# TI_TS5Axx.net
KiCad netlist of a schematic drawn in EAGLE
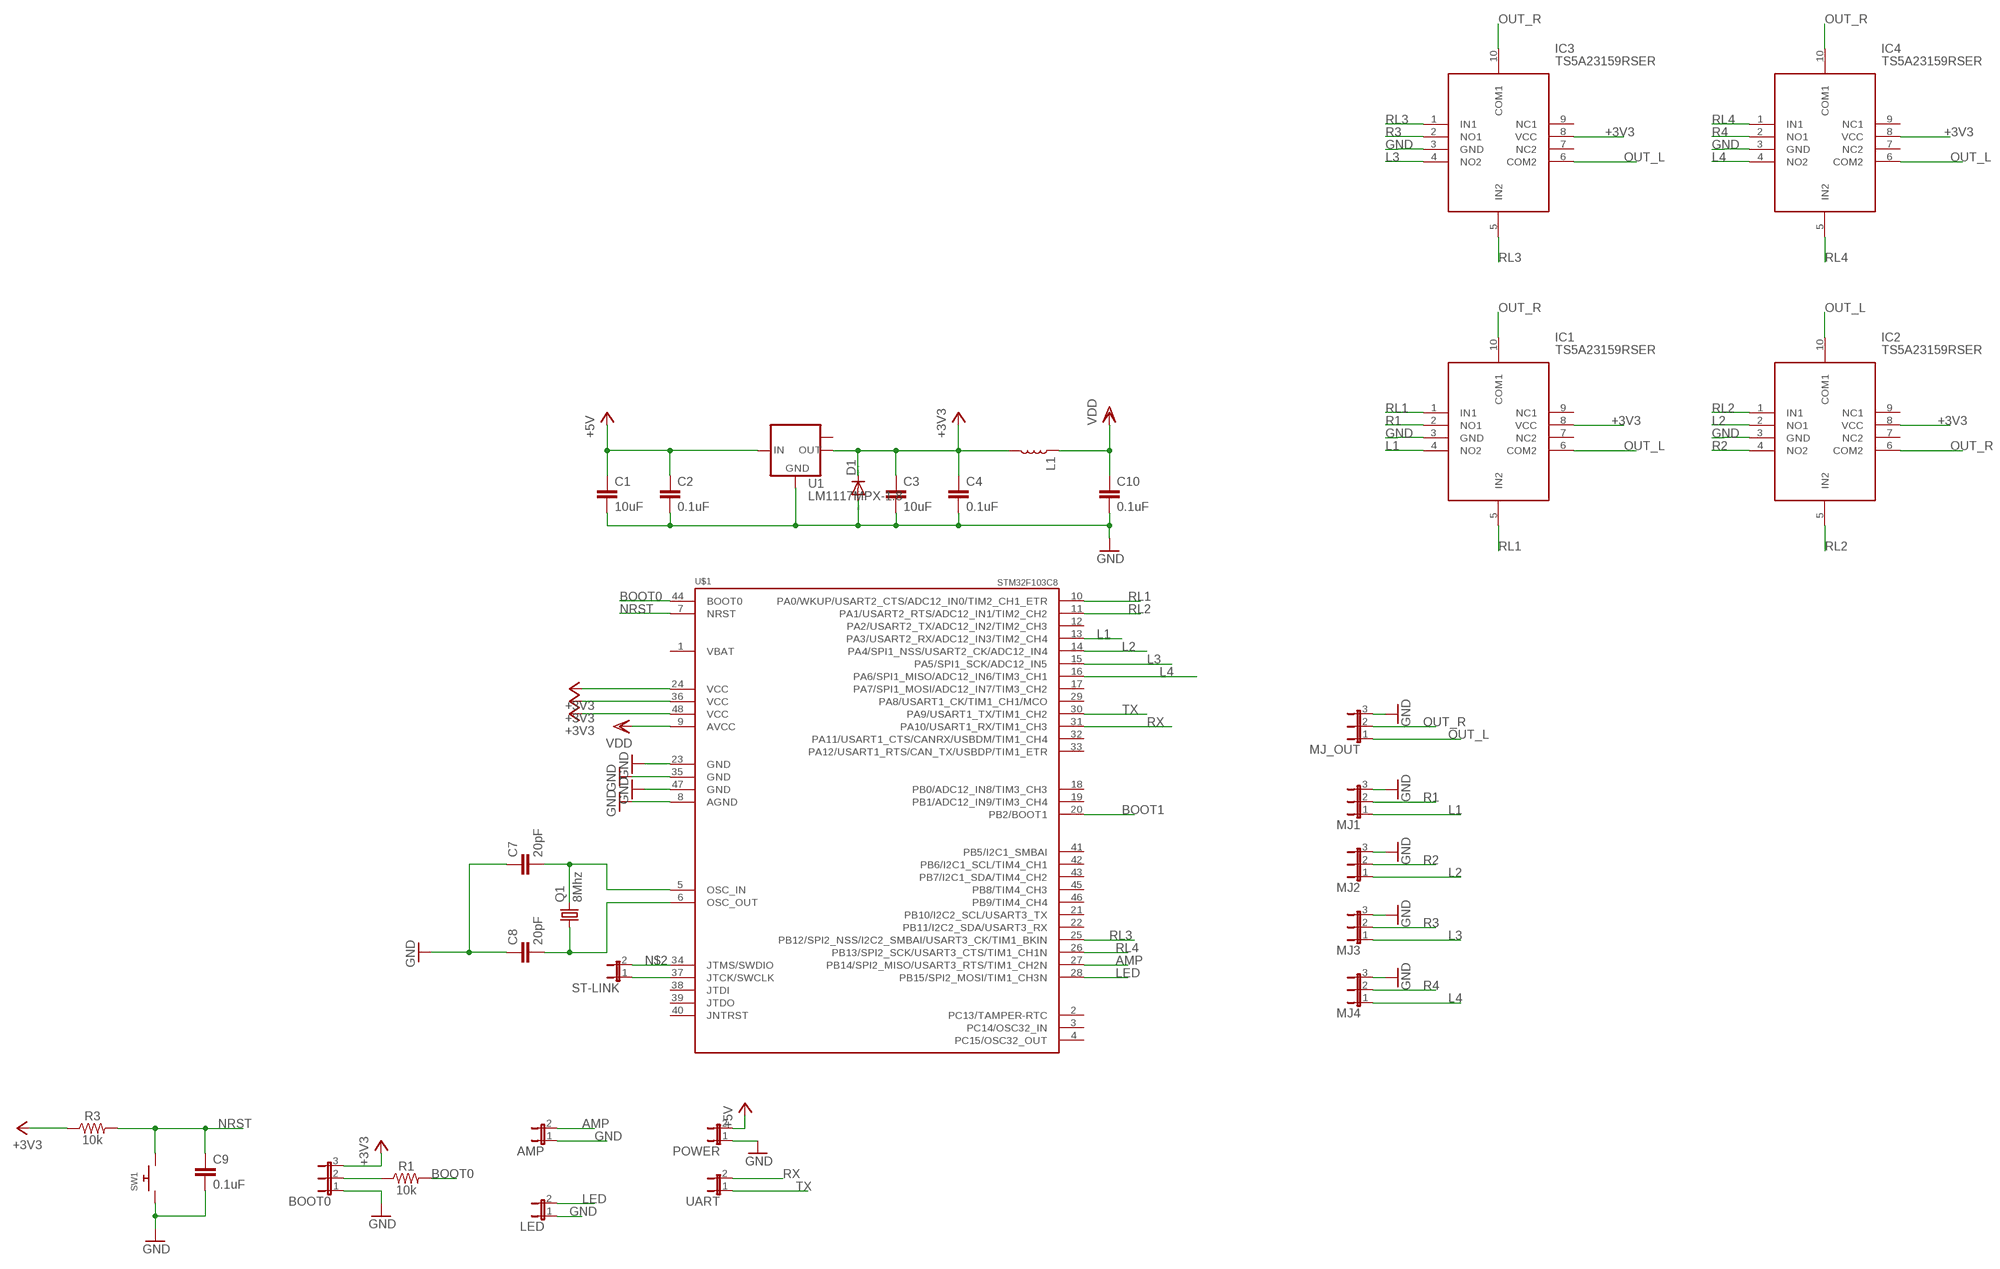
[diagram p0: schematic, sheet 1]

(export (version "E")
  (design (tool "Eeschema 10.0.6"))
  (components
    (comp (ref "AMP")
      (value "JP1E")
      (footprint "eagle-import:JP1")
      (libsource (lib "eagle-import") (part "JP1E"))
    )
    (comp (ref "BOOT0")
      (value "JP2E")
      (footprint "eagle-import:JP2")
      (libsource (lib "eagle-import") (part "JP2E"))
    )
    (comp (ref "C1")
      (value "10uF")
      (footprint "eagle-import:0805")
      (libsource (lib "eagle-import") (part "10UF-0805-10V-10%"))
    )
    (comp (ref "C2")
      (value "0.1uF")
      (footprint "eagle-import:0805")
      (libsource (lib "eagle-import") (part "10UF-0805-10V-10%"))
    )
    (comp (ref "C3")
      (value "10uF")
      (footprint "eagle-import:0805")
      (libsource (lib "eagle-import") (part "10UF-0805-10V-10%"))
    )
    (comp (ref "C4")
      (value "0.1uF")
      (footprint "eagle-import:0805")
      (libsource (lib "eagle-import") (part "10UF-0805-10V-10%"))
    )
    (comp (ref "C7")
      (value "20pF")
      (footprint "eagle-import:0805")
      (libsource (lib "eagle-import") (part "0.33UF/330NF-0805-50V-10%"))
    )
    (comp (ref "C8")
      (value "20pF")
      (footprint "eagle-import:0805")
      (libsource (lib "eagle-import") (part "0.33UF/330NF-0805-50V-10%"))
    )
    (comp (ref "C9")
      (value "0.1uF")
      (footprint "eagle-import:0805")
      (libsource (lib "eagle-import") (part "10UF-0805-10V-10%"))
    )
    (comp (ref "C10")
      (value "0.1uF")
      (footprint "eagle-import:0805")
      (libsource (lib "eagle-import") (part "10UF-0805-10V-10%"))
    )
    (comp (ref "D1")
      (value "DIODE-DO214AA")
      (footprint "eagle-import:DO214AA")
      (libsource (lib "eagle-import") (part "DIODE-DO214AA"))
    )
    (comp (ref "IC1")
      (value "TS5A23159RSER")
      (footprint "eagle-import:QFN50P150X200X60-10N")
      (libsource (lib "eagle-import") (part "TS5A23159RSER"))
    )
    (comp (ref "IC2")
      (value "TS5A23159RSER")
      (footprint "eagle-import:QFN50P150X200X60-10N")
      (libsource (lib "eagle-import") (part "TS5A23159RSER"))
    )
    (comp (ref "IC3")
      (value "TS5A23159RSER")
      (footprint "eagle-import:QFN50P150X200X60-10N")
      (libsource (lib "eagle-import") (part "TS5A23159RSER"))
    )
    (comp (ref "IC4")
      (value "TS5A23159RSER")
      (footprint "eagle-import:QFN50P150X200X60-10N")
      (libsource (lib "eagle-import") (part "TS5A23159RSER"))
    )
    (comp (ref "L1")
      (value "INDUCTORFB-30OHM")
      (footprint "eagle-import:0603")
      (libsource (lib "eagle-import") (part "INDUCTORFB-30OHM"))
    )
    (comp (ref "LED")
      (value "JP1E")
      (footprint "eagle-import:JP1")
      (libsource (lib "eagle-import") (part "JP1E"))
    )
    (comp (ref "MJ1")
      (value "JP2E")
      (footprint "eagle-import:JP2")
      (libsource (lib "eagle-import") (part "JP2E"))
    )
    (comp (ref "MJ2")
      (value "JP2E")
      (footprint "eagle-import:JP2")
      (libsource (lib "eagle-import") (part "JP2E"))
    )
    (comp (ref "MJ3")
      (value "JP2E")
      (footprint "eagle-import:JP2")
      (libsource (lib "eagle-import") (part "JP2E"))
    )
    (comp (ref "MJ4")
      (value "JP2E")
      (footprint "eagle-import:JP2")
      (libsource (lib "eagle-import") (part "JP2E"))
    )
    (comp (ref "MJ_OUT")
      (value "JP2E")
      (footprint "eagle-import:JP2")
      (libsource (lib "eagle-import") (part "JP2E"))
    )
    (comp (ref "POWER")
      (value "JP1E")
      (footprint "eagle-import:JP1")
      (libsource (lib "eagle-import") (part "JP1E"))
    )
    (comp (ref "Q1")
      (value "8Mhz")
      (footprint "eagle-import:HC49_S")
      (libsource (lib "eagle-import") (part "CRYSTALHC49S"))
    )
    (comp (ref "R1")
      (value "10k")
      (footprint "eagle-import:0603")
      (libsource (lib "eagle-import") (part "10KOHM-0603-1/10W-1%"))
    )
    (comp (ref "R3")
      (value "10k")
      (footprint "eagle-import:0603")
      (libsource (lib "eagle-import") (part "10KOHM-0603-1/10W-1%"))
    )
    (comp (ref "ST-LINK")
      (value "JP1E")
      (footprint "eagle-import:JP1")
      (libsource (lib "eagle-import") (part "JP1E"))
    )
    (comp (ref "SW1")
      (value "SWITCH_PUSHBUTTONEVQ-PE")
      (footprint "eagle-import:TACT_PANA-EVQ")
      (libsource (lib "eagle-import") (part "SWITCH_PUSHBUTTONEVQ-PE"))
    )
    (comp (ref "U$1")
      (value "STM32F103C8")
      (footprint "eagle-import:LQFP48-7X7")
      (libsource (lib "eagle-import") (part "STM32F103C8"))
    )
    (comp (ref "U1")
      (value "LM1117MPX-1.8")
      (footprint "eagle-import:SOT223")
      (libsource (lib "eagle-import") (part "LM1117MPX-1.8"))
    )
    (comp (ref "UART")
      (value "JP1E")
      (footprint "eagle-import:JP1")
      (libsource (lib "eagle-import") (part "JP1E"))
    )
  )
  (nets
    (net (code "1") (name "+3V3") (class "Default")
      (node (ref "BOOT0") (pin "3") (pinfunction "3_3") (pintype "passive"))
      (node (ref "C3") (pin "1") (pinfunction "1_1") (pintype "passive"))
      (node (ref "C4") (pin "1") (pinfunction "1_1") (pintype "passive"))
      (node (ref "D1") (pin "C") (pinfunction "C_C") (pintype "passive"))
      (node (ref "IC1") (pin "8") (pinfunction "VCC_8") (pintype "bidirectional"))
      (node (ref "IC2") (pin "8") (pinfunction "VCC_8") (pintype "bidirectional"))
      (node (ref "IC3") (pin "8") (pinfunction "VCC_8") (pintype "bidirectional"))
      (node (ref "IC4") (pin "8") (pinfunction "VCC_8") (pintype "bidirectional"))
      (node (ref "L1") (pin "2") (pinfunction "2_2") (pintype "passive"))
      (node (ref "R3") (pin "1") (pinfunction "1_1") (pintype "passive"))
      (node (ref "U$1") (pin "24") (pinfunction "VCC_24") (pintype "power_in"))
      (node (ref "U$1") (pin "36") (pinfunction "VCC_36") (pintype "power_in"))
      (node (ref "U$1") (pin "48") (pinfunction "VCC_48") (pintype "power_in"))
      (node (ref "U1") (pin "2") (pinfunction "OUT_2") (pintype "passive"))
    )
    (net (code "2") (name "+5V") (class "Default")
      (node (ref "C1") (pin "1") (pinfunction "1_1") (pintype "passive"))
      (node (ref "C2") (pin "1") (pinfunction "1_1") (pintype "passive"))
      (node (ref "POWER") (pin "2") (pinfunction "2_2") (pintype "passive"))
      (node (ref "U1") (pin "3") (pinfunction "IN_3") (pintype "input"))
    )
    (net (code "3") (name "/AMP") (class "Default")
      (node (ref "AMP") (pin "2") (pinfunction "2_2") (pintype "passive"))
      (node (ref "U$1") (pin "27") (pinfunction "PB14/SPI2_MISO/USART3_RTS/TIM1_CH2N_27") (pintype "bidirectional"))
    )
    (net (code "4") (name "/BOOT0") (class "Default")
      (node (ref "R1") (pin "2") (pinfunction "2_2") (pintype "passive"))
      (node (ref "U$1") (pin "44") (pinfunction "BOOT0_44") (pintype "bidirectional"))
    )
    (net (code "5") (name "/BOOT1") (class "Default")
      (node (ref "U$1") (pin "20") (pinfunction "PB2/BOOT1_20") (pintype "bidirectional"))
    )
    (net (code "6") (name "/L1") (class "Default")
      (node (ref "IC1") (pin "4") (pinfunction "NO2_4") (pintype "bidirectional"))
      (node (ref "MJ1") (pin "1") (pinfunction "1_1") (pintype "passive"))
      (node (ref "U$1") (pin "13") (pinfunction "PA3/USART2_RX/ADC12_IN3/TIM2_CH4_13") (pintype "bidirectional"))
    )
    (net (code "7") (name "/L2") (class "Default")
      (node (ref "IC2") (pin "2") (pinfunction "NO1_2") (pintype "bidirectional"))
      (node (ref "MJ2") (pin "1") (pinfunction "1_1") (pintype "passive"))
      (node (ref "U$1") (pin "14") (pinfunction "PA4/SPI1_NSS/USART2_CK/ADC12_IN4_14") (pintype "bidirectional"))
    )
    (net (code "8") (name "/L3") (class "Default")
      (node (ref "IC3") (pin "4") (pinfunction "NO2_4") (pintype "bidirectional"))
      (node (ref "MJ3") (pin "1") (pinfunction "1_1") (pintype "passive"))
      (node (ref "U$1") (pin "15") (pinfunction "PA5/SPI1_SCK/ADC12_IN5_15") (pintype "bidirectional"))
    )
    (net (code "9") (name "/L4") (class "Default")
      (node (ref "IC4") (pin "4") (pinfunction "NO2_4") (pintype "bidirectional"))
      (node (ref "MJ4") (pin "1") (pinfunction "1_1") (pintype "passive"))
      (node (ref "U$1") (pin "16") (pinfunction "PA6/SPI1_MISO/ADC12_IN6/TIM3_CH1_16") (pintype "bidirectional"))
    )
    (net (code "10") (name "/LED") (class "Default")
      (node (ref "LED") (pin "2") (pinfunction "2_2") (pintype "passive"))
      (node (ref "U$1") (pin "28") (pinfunction "PB15/SPI2_MOSI/TIM1_CH3N_28") (pintype "bidirectional"))
    )
    (net (code "11") (name "/N$2") (class "Default")
      (node (ref "ST-LINK") (pin "2") (pinfunction "2_2") (pintype "passive"))
      (node (ref "U$1") (pin "34") (pinfunction "JTMS/SWDIO_34") (pintype "bidirectional"))
    )
    (net (code "12") (name "/NRST") (class "Default")
      (node (ref "C9") (pin "1") (pinfunction "1_1") (pintype "passive"))
      (node (ref "R3") (pin "2") (pinfunction "2_2") (pintype "passive"))
      (node (ref "SW1") (pin "P$2") (pinfunction "P$2_P$2") (pintype "passive"))
      (node (ref "U$1") (pin "7") (pinfunction "NRST_7") (pintype "bidirectional"))
    )
    (net (code "13") (name "/OUT_L") (class "Default")
      (node (ref "IC1") (pin "6") (pinfunction "COM2_6") (pintype "bidirectional"))
      (node (ref "IC2") (pin "10") (pinfunction "COM1_10") (pintype "bidirectional"))
      (node (ref "IC3") (pin "6") (pinfunction "COM2_6") (pintype "bidirectional"))
      (node (ref "IC4") (pin "6") (pinfunction "COM2_6") (pintype "bidirectional"))
      (node (ref "MJ_OUT") (pin "1") (pinfunction "1_1") (pintype "passive"))
    )
    (net (code "14") (name "/OUT_R") (class "Default")
      (node (ref "IC1") (pin "10") (pinfunction "COM1_10") (pintype "bidirectional"))
      (node (ref "IC2") (pin "6") (pinfunction "COM2_6") (pintype "bidirectional"))
      (node (ref "IC3") (pin "10") (pinfunction "COM1_10") (pintype "bidirectional"))
      (node (ref "IC4") (pin "10") (pinfunction "COM1_10") (pintype "bidirectional"))
      (node (ref "MJ_OUT") (pin "2") (pinfunction "2_2") (pintype "passive"))
    )
    (net (code "15") (name "/R1") (class "Default")
      (node (ref "IC1") (pin "2") (pinfunction "NO1_2") (pintype "bidirectional"))
      (node (ref "MJ1") (pin "2") (pinfunction "2_2") (pintype "passive"))
    )
    (net (code "16") (name "/R2") (class "Default")
      (node (ref "IC2") (pin "4") (pinfunction "NO2_4") (pintype "bidirectional"))
      (node (ref "MJ2") (pin "2") (pinfunction "2_2") (pintype "passive"))
    )
    (net (code "17") (name "/R3") (class "Default")
      (node (ref "IC3") (pin "2") (pinfunction "NO1_2") (pintype "bidirectional"))
      (node (ref "MJ3") (pin "2") (pinfunction "2_2") (pintype "passive"))
    )
    (net (code "18") (name "/R4") (class "Default")
      (node (ref "IC4") (pin "2") (pinfunction "NO1_2") (pintype "bidirectional"))
      (node (ref "MJ4") (pin "2") (pinfunction "2_2") (pintype "passive"))
    )
    (net (code "19") (name "/RL1") (class "Default")
      (node (ref "IC1") (pin "1") (pinfunction "IN1_1") (pintype "bidirectional"))
      (node (ref "IC1") (pin "5") (pinfunction "IN2_5") (pintype "bidirectional"))
      (node (ref "U$1") (pin "10") (pinfunction "PA0/WKUP/USART2_CTS/ADC12_IN0/TIM2_CH1_ETR_10") (pintype "bidirectional"))
    )
    (net (code "20") (name "/RL2") (class "Default")
      (node (ref "IC2") (pin "1") (pinfunction "IN1_1") (pintype "bidirectional"))
      (node (ref "IC2") (pin "5") (pinfunction "IN2_5") (pintype "bidirectional"))
      (node (ref "U$1") (pin "11") (pinfunction "PA1/USART2_RTS/ADC12_IN1/TIM2_CH2_11") (pintype "bidirectional"))
    )
    (net (code "21") (name "/RL3") (class "Default")
      (node (ref "IC3") (pin "1") (pinfunction "IN1_1") (pintype "bidirectional"))
      (node (ref "IC3") (pin "5") (pinfunction "IN2_5") (pintype "bidirectional"))
      (node (ref "U$1") (pin "25") (pinfunction "PB12/SPI2_NSS/I2C2_SMBAI/USART3_CK/TIM1_BKIN_25") (pintype "bidirectional"))
    )
    (net (code "22") (name "/RL4") (class "Default")
      (node (ref "IC4") (pin "1") (pinfunction "IN1_1") (pintype "bidirectional"))
      (node (ref "IC4") (pin "5") (pinfunction "IN2_5") (pintype "bidirectional"))
      (node (ref "U$1") (pin "26") (pinfunction "PB13/SPI2_SCK/USART3_CTS/TIM1_CH1N_26") (pintype "bidirectional"))
    )
    (net (code "23") (name "/RX") (class "Default")
      (node (ref "U$1") (pin "31") (pinfunction "PA10/USART1_RX/TIM1_CH3_31") (pintype "bidirectional"))
      (node (ref "UART") (pin "2") (pinfunction "2_2") (pintype "passive"))
    )
    (net (code "24") (name "/TX") (class "Default")
      (node (ref "U$1") (pin "30") (pinfunction "PA9/USART1_TX/TIM1_CH2_30") (pintype "bidirectional"))
      (node (ref "UART") (pin "1") (pinfunction "1_1") (pintype "passive"))
    )
    (net (code "25") (name "/VBAT") (class "Default")
      (node (ref "U$1") (pin "1") (pinfunction "VBAT_1") (pintype "power_in"))
    )
    (net (code "26") (name "GND") (class "Default")
      (node (ref "AMP") (pin "1") (pinfunction "1_1") (pintype "passive"))
      (node (ref "BOOT0") (pin "1") (pinfunction "1_1") (pintype "passive"))
      (node (ref "C1") (pin "2") (pinfunction "2_2") (pintype "passive"))
      (node (ref "C10") (pin "2") (pinfunction "2_2") (pintype "passive"))
      (node (ref "C2") (pin "2") (pinfunction "2_2") (pintype "passive"))
      (node (ref "C3") (pin "2") (pinfunction "2_2") (pintype "passive"))
      (node (ref "C4") (pin "2") (pinfunction "2_2") (pintype "passive"))
      (node (ref "C7") (pin "1") (pinfunction "1_1") (pintype "passive"))
      (node (ref "C8") (pin "1") (pinfunction "1_1") (pintype "passive"))
      (node (ref "C9") (pin "2") (pinfunction "2_2") (pintype "passive"))
      (node (ref "D1") (pin "A") (pinfunction "A_A") (pintype "passive"))
      (node (ref "IC1") (pin "3") (pinfunction "GND_3") (pintype "bidirectional"))
      (node (ref "IC2") (pin "3") (pinfunction "GND_3") (pintype "bidirectional"))
      (node (ref "IC3") (pin "3") (pinfunction "GND_3") (pintype "bidirectional"))
      (node (ref "IC4") (pin "3") (pinfunction "GND_3") (pintype "bidirectional"))
      (node (ref "LED") (pin "1") (pinfunction "1_1") (pintype "passive"))
      (node (ref "MJ1") (pin "3") (pinfunction "3_3") (pintype "passive"))
      (node (ref "MJ2") (pin "3") (pinfunction "3_3") (pintype "passive"))
      (node (ref "MJ3") (pin "3") (pinfunction "3_3") (pintype "passive"))
      (node (ref "MJ4") (pin "3") (pinfunction "3_3") (pintype "passive"))
      (node (ref "MJ_OUT") (pin "3") (pinfunction "3_3") (pintype "passive"))
      (node (ref "POWER") (pin "1") (pinfunction "1_1") (pintype "passive"))
      (node (ref "SW1") (pin "P$1") (pinfunction "P$1_P$1") (pintype "passive"))
      (node (ref "U$1") (pin "23") (pinfunction "GND_23") (pintype "power_in"))
      (node (ref "U$1") (pin "35") (pinfunction "GND_35") (pintype "power_in"))
      (node (ref "U$1") (pin "47") (pinfunction "GND_47") (pintype "power_in"))
      (node (ref "U$1") (pin "8") (pinfunction "AGND_8") (pintype "power_in"))
      (node (ref "U1") (pin "1") (pinfunction "GND_1") (pintype "input"))
    )
    (net (code "27") (name "Net-(BOOT0-Pad2)") (class "Default")
      (node (ref "BOOT0") (pin "2") (pinfunction "2_2") (pintype "passive"))
      (node (ref "R1") (pin "1") (pinfunction "1_1") (pintype "passive"))
    )
    (net (code "28") (name "Net-(U$1-JTCK{slash}SWCLK)") (class "Default")
      (node (ref "ST-LINK") (pin "1") (pinfunction "1_1") (pintype "passive"))
      (node (ref "U$1") (pin "37") (pinfunction "JTCK/SWCLK_37") (pintype "bidirectional"))
    )
    (net (code "29") (name "Net-(U$1-OSC_IN)") (class "Default")
      (node (ref "C7") (pin "2") (pinfunction "2_2") (pintype "passive"))
      (node (ref "Q1") (pin "2") (pinfunction "2_2") (pintype "passive"))
      (node (ref "U$1") (pin "5") (pinfunction "OSC_IN_5") (pintype "input"))
    )
    (net (code "30") (name "Net-(U$1-OSC_OUT)") (class "Default")
      (node (ref "C8") (pin "2") (pinfunction "2_2") (pintype "passive"))
      (node (ref "Q1") (pin "1") (pinfunction "1_1") (pintype "passive"))
      (node (ref "U$1") (pin "6") (pinfunction "OSC_OUT_6") (pintype "output"))
    )
    (net (code "31") (name "VDD") (class "Default")
      (node (ref "C10") (pin "1") (pinfunction "1_1") (pintype "passive"))
      (node (ref "L1") (pin "1") (pinfunction "1_1") (pintype "passive"))
      (node (ref "U$1") (pin "9") (pinfunction "AVCC_9") (pintype "power_in"))
    )
    (net (code "32") (name "unconnected-(IC1-NC1-Pad9)") (class "Default")
      (node (ref "IC1") (pin "9") (pinfunction "NC1_9") (pintype "bidirectional"))
    )
    (net (code "33") (name "unconnected-(IC1-NC2-Pad7)") (class "Default")
      (node (ref "IC1") (pin "7") (pinfunction "NC2_7") (pintype "bidirectional"))
    )
    (net (code "34") (name "unconnected-(IC2-NC1-Pad9)") (class "Default")
      (node (ref "IC2") (pin "9") (pinfunction "NC1_9") (pintype "bidirectional"))
    )
    (net (code "35") (name "unconnected-(IC2-NC2-Pad7)") (class "Default")
      (node (ref "IC2") (pin "7") (pinfunction "NC2_7") (pintype "bidirectional"))
    )
    (net (code "36") (name "unconnected-(IC3-NC1-Pad9)") (class "Default")
      (node (ref "IC3") (pin "9") (pinfunction "NC1_9") (pintype "bidirectional"))
    )
    (net (code "37") (name "unconnected-(IC3-NC2-Pad7)") (class "Default")
      (node (ref "IC3") (pin "7") (pinfunction "NC2_7") (pintype "bidirectional"))
    )
    (net (code "38") (name "unconnected-(IC4-NC1-Pad9)") (class "Default")
      (node (ref "IC4") (pin "9") (pinfunction "NC1_9") (pintype "bidirectional"))
    )
    (net (code "39") (name "unconnected-(IC4-NC2-Pad7)") (class "Default")
      (node (ref "IC4") (pin "7") (pinfunction "NC2_7") (pintype "bidirectional"))
    )
    (net (code "40") (name "unconnected-(U$1-JNTRST-Pad40)") (class "Default")
      (node (ref "U$1") (pin "40") (pinfunction "JNTRST_40") (pintype "bidirectional"))
    )
    (net (code "41") (name "unconnected-(U$1-JTDI-Pad38)") (class "Default")
      (node (ref "U$1") (pin "38") (pinfunction "JTDI_38") (pintype "bidirectional"))
    )
    (net (code "42") (name "unconnected-(U$1-JTDO-Pad39)") (class "Default")
      (node (ref "U$1") (pin "39") (pinfunction "JTDO_39") (pintype "bidirectional"))
    )
    (net (code "43") (name "unconnected-(U$1-PA2{slash}USART2_TX{slash}ADC12_IN2{slash}TIM2_CH3-Pad12)") (class "Default")
      (node (ref "U$1") (pin "12") (pinfunction "PA2/USART2_TX/ADC12_IN2/TIM2_CH3_12") (pintype "bidirectional"))
    )
    (net (code "44") (name "unconnected-(U$1-PA7{slash}SPI1_MOSI{slash}ADC12_IN7{slash}TIM3_CH2-Pad17)") (class "Default")
      (node (ref "U$1") (pin "17") (pinfunction "PA7/SPI1_MOSI/ADC12_IN7/TIM3_CH2_17") (pintype "bidirectional"))
    )
    (net (code "45") (name "unconnected-(U$1-PA8{slash}USART1_CK{slash}TIM1_CH1{slash}MCO-Pad29)") (class "Default")
      (node (ref "U$1") (pin "29") (pinfunction "PA8/USART1_CK/TIM1_CH1/MCO_29") (pintype "bidirectional"))
    )
    (net (code "46") (name "unconnected-(U$1-PA11{slash}USART1_CTS{slash}CANRX{slash}USBDM{slash}TIM1_CH4-Pad32)") (class "Default")
      (node (ref "U$1") (pin "32") (pinfunction "PA11/USART1_CTS/CANRX/USBDM/TIM1_CH4_32") (pintype "bidirectional"))
    )
    (net (code "47") (name "unconnected-(U$1-PA12{slash}USART1_RTS{slash}CAN_TX{slash}USBDP{slash}TIM1_ETR-Pad33)") (class "Default")
      (node (ref "U$1") (pin "33") (pinfunction "PA12/USART1_RTS/CAN_TX/USBDP/TIM1_ETR_33") (pintype "bidirectional"))
    )
    (net (code "48") (name "unconnected-(U$1-PB0{slash}ADC12_IN8{slash}TIM3_CH3-Pad18)") (class "Default")
      (node (ref "U$1") (pin "18") (pinfunction "PB0/ADC12_IN8/TIM3_CH3_18") (pintype "bidirectional"))
    )
    (net (code "49") (name "unconnected-(U$1-PB1{slash}ADC12_IN9{slash}TIM3_CH4-Pad19)") (class "Default")
      (node (ref "U$1") (pin "19") (pinfunction "PB1/ADC12_IN9/TIM3_CH4_19") (pintype "bidirectional"))
    )
    (net (code "50") (name "unconnected-(U$1-PB5{slash}I2C1_SMBAI-Pad41)") (class "Default")
      (node (ref "U$1") (pin "41") (pinfunction "PB5/I2C1_SMBAI_41") (pintype "bidirectional"))
    )
    (net (code "51") (name "unconnected-(U$1-PB6{slash}I2C1_SCL{slash}TIM4_CH1-Pad42)") (class "Default")
      (node (ref "U$1") (pin "42") (pinfunction "PB6/I2C1_SCL/TIM4_CH1_42") (pintype "bidirectional"))
    )
    (net (code "52") (name "unconnected-(U$1-PB7{slash}I2C1_SDA{slash}TIM4_CH2-Pad43)") (class "Default")
      (node (ref "U$1") (pin "43") (pinfunction "PB7/I2C1_SDA/TIM4_CH2_43") (pintype "bidirectional"))
    )
    (net (code "53") (name "unconnected-(U$1-PB8{slash}TIM4_CH3-Pad45)") (class "Default")
      (node (ref "U$1") (pin "45") (pinfunction "PB8/TIM4_CH3_45") (pintype "bidirectional"))
    )
    (net (code "54") (name "unconnected-(U$1-PB9{slash}TIM4_CH4-Pad46)") (class "Default")
      (node (ref "U$1") (pin "46") (pinfunction "PB9/TIM4_CH4_46") (pintype "bidirectional"))
    )
    (net (code "55") (name "unconnected-(U$1-PB10{slash}I2C2_SCL{slash}USART3_TX-Pad21)") (class "Default")
      (node (ref "U$1") (pin "21") (pinfunction "PB10/I2C2_SCL/USART3_TX_21") (pintype "bidirectional"))
    )
    (net (code "56") (name "unconnected-(U$1-PB11{slash}I2C2_SDA{slash}USART3_RX-Pad22)") (class "Default")
      (node (ref "U$1") (pin "22") (pinfunction "PB11/I2C2_SDA/USART3_RX_22") (pintype "bidirectional"))
    )
    (net (code "57") (name "unconnected-(U$1-PC13{slash}TAMPER-RTC-Pad2)") (class "Default")
      (node (ref "U$1") (pin "2") (pinfunction "PC13/TAMPER-RTC_2") (pintype "bidirectional"))
    )
    (net (code "58") (name "unconnected-(U$1-PC14{slash}OSC32_IN-Pad3)") (class "Default")
      (node (ref "U$1") (pin "3") (pinfunction "PC14/OSC32_IN_3") (pintype "bidirectional"))
    )
    (net (code "59") (name "unconnected-(U$1-PC15{slash}OSC32_OUT-Pad4)") (class "Default")
      (node (ref "U$1") (pin "4") (pinfunction "PC15/OSC32_OUT_4") (pintype "bidirectional"))
    )
    (net (code "60") (name "unconnected-(U1-OUT1-PadTAB)") (class "Default")
      (node (ref "U1") (pin "TAB") (pinfunction "OUT1_TAB") (pintype "passive"))
    )
  )
)
